# IR_TSOP95438.net
KiCad netlist of a schematic drawn in Altium Designer
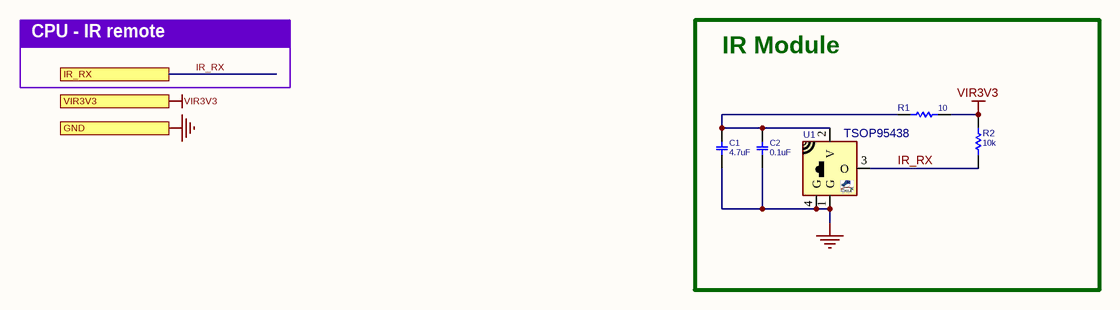
[diagram p0: IR_TSOP95438.SchDoc]

(export (version "E")
  (design (tool "Eeschema 10.0.6"))
  (components
    (comp (ref "C1")
      (value "4.7uF")
      (footprint "C0402")
      (description "CAP, MLCC")
      (fields (field (name "MANF_P#") "CL05A475MP5NRNC") (field (name "MANF") "Samsung"))
      (libsource (lib "passive_smd") (part "CAP_SMD_MLCC"))
    )
    (comp (ref "C2")
      (value "0.1uF")
      (footprint "C0402")
      (description "CAP, MLCC")
      (fields (field (name "MANF_P#") "GRM155R61E104") (field (name "MANF") "Murata"))
      (libsource (lib "passive_smd") (part "CAP_SMD_MLCC"))
    )
    (comp (ref "R1")
      (value "10")
      (footprint "R0402")
      (description "RESISTOR, SMD")
      (libsource (lib "passive_res_smd") (part "RES_SMD"))
    )
    (comp (ref "R2")
      (value "10k")
      (footprint "R0402")
      (description "RESISTOR, SMD")
      (libsource (lib "passive_res_smd") (part "RES_SMD"))
    )
    (comp (ref "U1")
      (value "TSOP95438")
      (footprint "PHM_TSOPHEIMDALL")
      (description "IR Receiver Modules for Remote Control Systems")
      (fields (field (name "MANF") "VISHAY"))
      (libsource (lib "sensor_light") (part "PHM_TSOP95438_Heimdall"))
    )
  )
  (nets
    (net (code "1") (name "/IR_RX") (class "Default")
      (node (ref "R2") (pin "1") (pinfunction "1_1") (pintype "passive"))
      (node (ref "U1") (pin "3") (pinfunction "O_3") (pintype "passive"))
    )
    (net (code "2") (name "GND") (class "Default")
      (node (ref "C1") (pin "1") (pinfunction "1_1") (pintype "passive"))
      (node (ref "C2") (pin "1") (pinfunction "1_1") (pintype "passive"))
      (node (ref "U1") (pin "1") (pinfunction "G_1") (pintype "passive"))
      (node (ref "U1") (pin "4") (pinfunction "G_4") (pintype "passive"))
    )
    (net (code "3") (name "Net-(U1-V)") (class "Default")
      (node (ref "C1") (pin "2") (pinfunction "2_2") (pintype "passive"))
      (node (ref "C2") (pin "2") (pinfunction "2_2") (pintype "passive"))
      (node (ref "R1") (pin "1") (pinfunction "1_1") (pintype "passive"))
      (node (ref "U1") (pin "2") (pinfunction "V_2") (pintype "passive"))
    )
    (net (code "4") (name "VIR3V3") (class "Default")
      (node (ref "R1") (pin "2") (pinfunction "2_2") (pintype "passive"))
      (node (ref "R2") (pin "2") (pinfunction "2_2") (pintype "passive"))
    )
  )
)
